# PCBWayPrototype.net
KiCad netlist of a schematic drawn in EAGLE
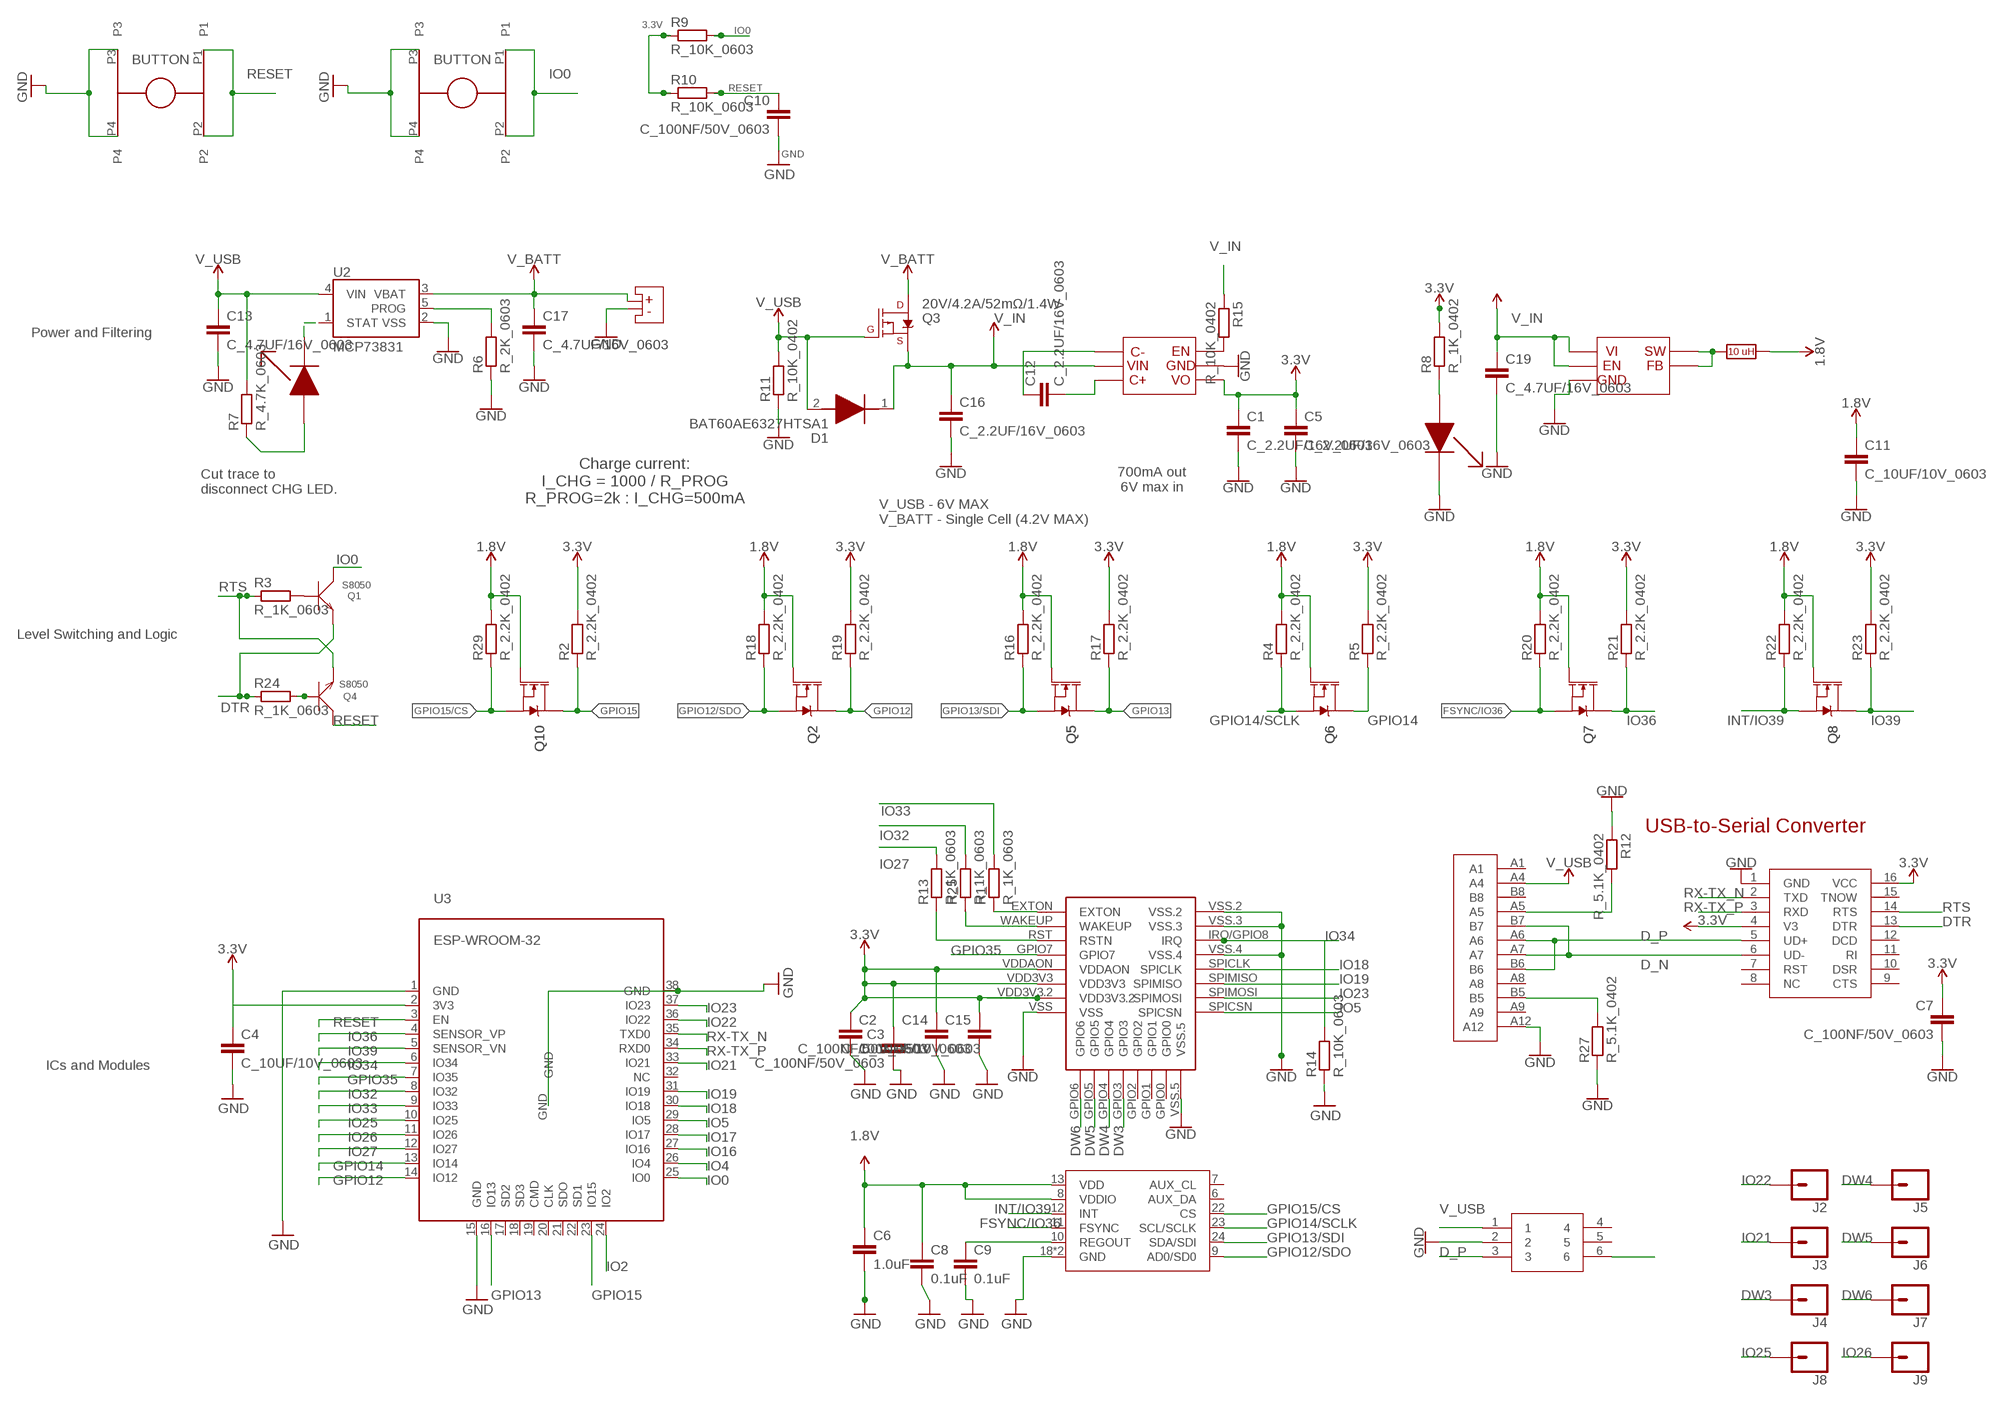
[diagram p0: schematic, sheet 1]

(export (version "E")
  (design (tool "Eeschema 10.0.6"))
  (components
    (comp (ref "C1")
      (value "C_2.2UF/16V_0603")
      (footprint "eagle-import:C0603")
      (fields (field (name "LCSC_PART") "C23630"))
      (libsource (lib "eagle-import") (part "C__06032.2UF/16V"))
    )
    (comp (ref "C2")
      (value "C_10UF/10V_0603")
      (footprint "eagle-import:C0603")
      (fields (field (name "LCSC_PART") "C19702"))
      (libsource (lib "eagle-import") (part "C__060310UF/10V"))
    )
    (comp (ref "C3")
      (value "C_100NF/50V_0603")
      (footprint "eagle-import:C0603")
      (fields (field (name "LCSC_PART") "C14663"))
      (libsource (lib "eagle-import") (part "C__0603100NF/50V"))
    )
    (comp (ref "C4")
      (value "C_10UF/10V_0603")
      (footprint "eagle-import:C0603")
      (fields (field (name "LCSC_PART") "C19702"))
      (libsource (lib "eagle-import") (part "C__060310UF/10V"))
    )
    (comp (ref "C5")
      (value "C_2.2UF/16V_0603")
      (footprint "eagle-import:C0603")
      (fields (field (name "LCSC_PART") "C23630"))
      (libsource (lib "eagle-import") (part "C__06032.2UF/16V"))
    )
    (comp (ref "C6")
      (value "1.0uF")
      (footprint "eagle-import:0603")
      (libsource (lib "eagle-import") (part "1.0UF-0603-16V-10%-X7R"))
    )
    (comp (ref "C7")
      (value "C_100NF/50V_0603")
      (footprint "eagle-import:C0603")
      (fields (field (name "LCSC_PART") "C14663"))
      (libsource (lib "eagle-import") (part "C__0603100NF/50V"))
    )
    (comp (ref "C8")
      (value "0.1uF")
      (footprint "eagle-import:0603")
      (libsource (lib "eagle-import") (part "0.1UF-0603-25V-5%"))
    )
    (comp (ref "C9")
      (value "0.1uF")
      (footprint "eagle-import:0603")
      (libsource (lib "eagle-import") (part "0.1UF-0603-25V-5%"))
    )
    (comp (ref "C10")
      (value "C_100NF/50V_0603")
      (footprint "eagle-import:C0603")
      (fields (field (name "LCSC_PART") "C14663"))
      (libsource (lib "eagle-import") (part "C__0603100NF/50V"))
    )
    (comp (ref "C11")
      (value "C_10UF/10V_0603")
      (footprint "eagle-import:C0603")
      (fields (field (name "LCSC_PART") "C19702"))
      (libsource (lib "eagle-import") (part "C__060310UF/10V"))
    )
    (comp (ref "C12")
      (value "C_2.2UF/16V_0603")
      (footprint "eagle-import:C0603")
      (fields (field (name "LCSC_PART") "C23630"))
      (libsource (lib "eagle-import") (part "C__06032.2UF/16V"))
    )
    (comp (ref "C13")
      (value "C_4.7UF/16V_0603")
      (footprint "eagle-import:C0603")
      (fields (field (name "LCSC_PART") "C19666"))
      (libsource (lib "eagle-import") (part "C__06034.7UF/16V"))
    )
    (comp (ref "C14")
      (value "C_100NF/50V_0603")
      (footprint "eagle-import:C0603")
      (fields (field (name "LCSC_PART") "C14663"))
      (libsource (lib "eagle-import") (part "C__0603100NF/50V"))
    )
    (comp (ref "C15")
      (value "C_100NF/50V_0603")
      (footprint "eagle-import:C0603")
      (fields (field (name "LCSC_PART") "C14663"))
      (libsource (lib "eagle-import") (part "C__0603100NF/50V"))
    )
    (comp (ref "C16")
      (value "C_2.2UF/16V_0603")
      (footprint "eagle-import:C0603")
      (fields (field (name "LCSC_PART") "C23630"))
      (libsource (lib "eagle-import") (part "C__06032.2UF/16V"))
    )
    (comp (ref "C17")
      (value "C_4.7UF/16V_0603")
      (footprint "eagle-import:C0603")
      (fields (field (name "LCSC_PART") "C19666"))
      (libsource (lib "eagle-import") (part "C__06034.7UF/16V"))
    )
    (comp (ref "C19")
      (value "C_4.7UF/16V_0603")
      (footprint "eagle-import:C0603")
      (fields (field (name "LCSC_PART") "C19666"))
      (libsource (lib "eagle-import") (part "C__06034.7UF/16V"))
    )
    (comp (ref "D1")
      (value "BAT60AE6327HTSA1")
      (footprint "eagle-import:SOD2513X110N")
      (fields (field (name "MOUSER_PART_NUMBER") "726-BAT60AE6327HTSA1"))
      (libsource (lib "eagle-import") (part "BAT60AE6327HTSA1"))
    )
    (comp (ref "J2")
      (value "CONN_01PTH_2MM")
      (footprint "eagle-import:1X01_2MM")
      (libsource (lib "eagle-import") (part "CONN_01PTH_2MM"))
    )
    (comp (ref "J3")
      (value "CONN_01PTH_2MM")
      (footprint "eagle-import:1X01_2MM")
      (libsource (lib "eagle-import") (part "CONN_01PTH_2MM"))
    )
    (comp (ref "J4")
      (value "CONN_01PTH_2MM")
      (footprint "eagle-import:1X01_2MM")
      (libsource (lib "eagle-import") (part "CONN_01PTH_2MM"))
    )
    (comp (ref "J5")
      (value "CONN_01PTH_2MM")
      (footprint "eagle-import:1X01_2MM")
      (libsource (lib "eagle-import") (part "CONN_01PTH_2MM"))
    )
    (comp (ref "J6")
      (value "CONN_01PTH_2MM")
      (footprint "eagle-import:1X01_2MM")
      (libsource (lib "eagle-import") (part "CONN_01PTH_2MM"))
    )
    (comp (ref "J7")
      (value "CONN_01PTH_2MM")
      (footprint "eagle-import:1X01_2MM")
      (libsource (lib "eagle-import") (part "CONN_01PTH_2MM"))
    )
    (comp (ref "J8")
      (value "CONN_01PTH_2MM")
      (footprint "eagle-import:1X01_2MM")
      (libsource (lib "eagle-import") (part "CONN_01PTH_2MM"))
    )
    (comp (ref "J9")
      (value "CONN_01PTH_2MM")
      (footprint "eagle-import:1X01_2MM")
      (libsource (lib "eagle-import") (part "CONN_01PTH_2MM"))
    )
    (comp (ref "Q1")
      (value "S8050")
      (footprint "eagle-import:SOT23")
      (libsource (lib "eagle-import") (part "TRANSISTOR-NPN-SOT23"))
    )
    (comp (ref "Q2")
      (value "20V/0.2A/8MHz/1.2Ω/1Vth")
      (footprint "eagle-import:SOT-416FL")
      (libsource (lib "eagle-import") (part "MOSFET-NCH-RE1C002UN"))
    )
    (comp (ref "Q3")
      (value "20V/4.2A/52mΩ/1.4W")
      (footprint "eagle-import:SOT23-3@1")
      (libsource (lib "eagle-import") (part "MOSFET_PCH-DMG2305UX-7"))
    )
    (comp (ref "Q4")
      (value "S8050")
      (footprint "eagle-import:SOT23")
      (libsource (lib "eagle-import") (part "TRANSISTOR-NPN-SOT23"))
    )
    (comp (ref "Q5")
      (value "20V/0.2A/8MHz/1.2Ω/1Vth")
      (footprint "eagle-import:SOT-416FL")
      (libsource (lib "eagle-import") (part "MOSFET-NCH-RE1C002UN"))
    )
    (comp (ref "Q6")
      (value "20V/0.2A/8MHz/1.2Ω/1Vth")
      (footprint "eagle-import:SOT-416FL")
      (libsource (lib "eagle-import") (part "MOSFET-NCH-RE1C002UN"))
    )
    (comp (ref "Q7")
      (value "20V/0.2A/8MHz/1.2Ω/1Vth")
      (footprint "eagle-import:SOT-416FL")
      (libsource (lib "eagle-import") (part "MOSFET-NCH-RE1C002UN"))
    )
    (comp (ref "Q8")
      (value "20V/0.2A/8MHz/1.2Ω/1Vth")
      (footprint "eagle-import:SOT-416FL")
      (libsource (lib "eagle-import") (part "MOSFET-NCH-RE1C002UN"))
    )
    (comp (ref "Q10")
      (value "20V/0.2A/8MHz/1.2Ω/1Vth")
      (footprint "eagle-import:SOT-416FL")
      (libsource (lib "eagle-import") (part "MOSFET-NCH-RE1C002UN"))
    )
    (comp (ref "R1")
      (value "R_1K_0603")
      (footprint "eagle-import:R0603")
      (fields (field (name "LCSC_PART") "C21190"))
      (libsource (lib "eagle-import") (part "R__06031K"))
    )
    (comp (ref "R2")
      (value "R_2.2K_0402")
      (footprint "eagle-import:R0402")
      (fields (field (name "LCSC_PART") "C25879"))
      (libsource (lib "eagle-import") (part "R__04022.2K"))
    )
    (comp (ref "R3")
      (value "R_1K_0603")
      (footprint "eagle-import:R0603")
      (fields (field (name "LCSC_PART") "C21190"))
      (libsource (lib "eagle-import") (part "R__06031K"))
    )
    (comp (ref "R4")
      (value "R_2.2K_0402")
      (footprint "eagle-import:R0402")
      (fields (field (name "LCSC_PART") "C25879"))
      (libsource (lib "eagle-import") (part "R__04022.2K"))
    )
    (comp (ref "R5")
      (value "R_2.2K_0402")
      (footprint "eagle-import:R0402")
      (fields (field (name "LCSC_PART") "C25879"))
      (libsource (lib "eagle-import") (part "R__04022.2K"))
    )
    (comp (ref "R6")
      (value "R_2K_0603")
      (footprint "eagle-import:R0603")
      (fields (field (name "LCSC_PART") "C22975"))
      (libsource (lib "eagle-import") (part "R__06032K"))
    )
    (comp (ref "R7")
      (value "R_4.7K_0603")
      (footprint "eagle-import:R0603")
      (fields (field (name "LCSC_PART") "C23162"))
      (libsource (lib "eagle-import") (part "R__06034.7K"))
    )
    (comp (ref "R8")
      (value "R_1K_0402")
      (footprint "eagle-import:R0402")
      (fields (field (name "LCSC_PART") "C11702"))
      (libsource (lib "eagle-import") (part "R__04021K"))
    )
    (comp (ref "R9")
      (value "R_10K_0603")
      (footprint "eagle-import:R0603")
      (fields (field (name "LCSC_PART") "C25804"))
      (libsource (lib "eagle-import") (part "R__060310K"))
    )
    (comp (ref "R10")
      (value "R_10K_0603")
      (footprint "eagle-import:R0603")
      (fields (field (name "LCSC_PART") "C25804"))
      (libsource (lib "eagle-import") (part "R__060310K"))
    )
    (comp (ref "R11")
      (value "R_10K_0402")
      (footprint "eagle-import:R0402")
      (fields (field (name "LCSC_PART") "C25744"))
      (libsource (lib "eagle-import") (part "R__040210K"))
    )
    (comp (ref "R12")
      (value "R_5.1K_0402")
      (footprint "eagle-import:R0402")
      (fields (field (name "LCSC_PART") "C25905"))
      (libsource (lib "eagle-import") (part "R__04025.1K"))
    )
    (comp (ref "R13")
      (value "R_1K_0603")
      (footprint "eagle-import:R0603")
      (fields (field (name "LCSC_PART") "C21190"))
      (libsource (lib "eagle-import") (part "R__06031K"))
    )
    (comp (ref "R14")
      (value "R_10K_0603")
      (footprint "eagle-import:R0603")
      (fields (field (name "LCSC_PART") "C25804"))
      (libsource (lib "eagle-import") (part "R__060310K"))
    )
    (comp (ref "R15")
      (value "R_10K_0402")
      (footprint "eagle-import:R0402")
      (fields (field (name "LCSC_PART") "C25744"))
      (libsource (lib "eagle-import") (part "R__040210K"))
    )
    (comp (ref "R16")
      (value "R_2.2K_0402")
      (footprint "eagle-import:R0402")
      (fields (field (name "LCSC_PART") "C25879"))
      (libsource (lib "eagle-import") (part "R__04022.2K"))
    )
    (comp (ref "R17")
      (value "R_2.2K_0402")
      (footprint "eagle-import:R0402")
      (fields (field (name "LCSC_PART") "C25879"))
      (libsource (lib "eagle-import") (part "R__04022.2K"))
    )
    (comp (ref "R18")
      (value "R_2.2K_0402")
      (footprint "eagle-import:R0402")
      (fields (field (name "LCSC_PART") "C25879"))
      (libsource (lib "eagle-import") (part "R__04022.2K"))
    )
    (comp (ref "R19")
      (value "R_2.2K_0402")
      (footprint "eagle-import:R0402")
      (fields (field (name "LCSC_PART") "C25879"))
      (libsource (lib "eagle-import") (part "R__04022.2K"))
    )
    (comp (ref "R20")
      (value "R_2.2K_0402")
      (footprint "eagle-import:R0402")
      (fields (field (name "LCSC_PART") "C25879"))
      (libsource (lib "eagle-import") (part "R__04022.2K"))
    )
    (comp (ref "R21")
      (value "R_2.2K_0402")
      (footprint "eagle-import:R0402")
      (fields (field (name "LCSC_PART") "C25879"))
      (libsource (lib "eagle-import") (part "R__04022.2K"))
    )
    (comp (ref "R22")
      (value "R_2.2K_0402")
      (footprint "eagle-import:R0402")
      (fields (field (name "LCSC_PART") "C25879"))
      (libsource (lib "eagle-import") (part "R__04022.2K"))
    )
    (comp (ref "R23")
      (value "R_2.2K_0402")
      (footprint "eagle-import:R0402")
      (fields (field (name "LCSC_PART") "C25879"))
      (libsource (lib "eagle-import") (part "R__04022.2K"))
    )
    (comp (ref "R24")
      (value "R_1K_0603")
      (footprint "eagle-import:R0603")
      (fields (field (name "LCSC_PART") "C21190"))
      (libsource (lib "eagle-import") (part "R__06031K"))
    )
    (comp (ref "R25")
      (value "R_1K_0603")
      (footprint "eagle-import:R0603")
      (fields (field (name "LCSC_PART") "C21190"))
      (libsource (lib "eagle-import") (part "R__06031K"))
    )
    (comp (ref "R27")
      (value "R_5.1K_0402")
      (footprint "eagle-import:R0402")
      (fields (field (name "LCSC_PART") "C25905"))
      (libsource (lib "eagle-import") (part "R__04025.1K"))
    )
    (comp (ref "R29")
      (value "R_2.2K_0402")
      (footprint "eagle-import:R0402")
      (fields (field (name "LCSC_PART") "C25879"))
      (libsource (lib "eagle-import") (part "R__04022.2K"))
    )
    (comp (ref "U$1")
      (value "K2-6639SP-C4SC-04_C83206")
      (footprint "eagle-import:K2-6639SP-C4SC-04")
      (libsource (lib "eagle-import") (part "K2-6639SP-C4SC-04_C83206"))
    )
    (comp (ref "U$2")
      (value "MLF2012")
      (footprint "eagle-import:MLF2012")
      (libsource (lib "eagle-import") (part "MLF2012"))
    )
    (comp (ref "U$3")
      (value "K2-6639SP-C4SC-04_C83206")
      (footprint "eagle-import:K2-6639SP-C4SC-04")
      (libsource (lib "eagle-import") (part "K2-6639SP-C4SC-04_C83206"))
    )
    (comp (ref "U$4")
      (value "TPS62202DBVR")
      (footprint "eagle-import:TPS62202DBVR")
      (libsource (lib "eagle-import") (part "TPS62202DBVR"))
    )
    (comp (ref "U$5")
      (value "HE9008M6R")
      (footprint "eagle-import:HE9008M6R")
      (libsource (lib "eagle-import") (part "HE9008M6R"))
    )
    (comp (ref "U$6")
      (value "19-217/GHC-YR1S2/3T")
      (footprint "eagle-import:19-217_GHC-YR1S2_3T")
      (libsource (lib "eagle-import") (part "19-217/GHC-YR1S2/3T"))
    )
    (comp (ref "U$7")
      (value "TPSMF05CT1G")
      (footprint "eagle-import:TPSMF05CT1G")
      (libsource (lib "eagle-import") (part "TPSMF05CT1G"))
    )
    (comp (ref "U$8")
      (value "SM02B_PASS_TB_LF")
      (footprint "eagle-import:SM02B_PASS_TB_LF")
      (libsource (lib "eagle-import") (part "SM02B_PASS_TB_LF"))
    )
    (comp (ref "U$9")
      (value "19-217/GHC-YR1S2/3T")
      (footprint "eagle-import:19-217_GHC-YR1S2_3T")
      (libsource (lib "eagle-import") (part "19-217/GHC-YR1S2/3T"))
    )
    (comp (ref "U$10")
      (value "USBC19")
      (footprint "eagle-import:USBC19")
      (libsource (lib "eagle-import") (part "USBC19"))
    )
    (comp (ref "U$11")
      (value "CH340B")
      (footprint "eagle-import:SOP-16")
      (libsource (lib "eagle-import") (part "CH340B"))
    )
    (comp (ref "U$12")
      (value "ICM20948")
      (footprint "eagle-import:ICM20948")
      (libsource (lib "eagle-import") (part "ICM20948"))
    )
    (comp (ref "U2")
      (value "MCP73831")
      (footprint "eagle-import:SOT23-5")
      (libsource (lib "eagle-import") (part "MCP73831"))
    )
    (comp (ref "U3")
      (value "ESP-WROOM-32")
      (footprint "eagle-import:ESP-WROOM-32")
      (libsource (lib "eagle-import") (part "ESP-WROOM-32"))
    )
    (comp (ref "U5")
      (value "DWM1000")
      (footprint "eagle-import:DWM1000")
      (libsource (lib "eagle-import") (part "DWM1000"))
    )
  )
  (nets
    (net (code "1") (name "/DTR") (class "Default")
      (node (ref "Q1") (pin "2") (pinfunction "E_2") (pintype "passive"))
      (node (ref "R24") (pin "1") (pinfunction "1_1") (pintype "passive"))
      (node (ref "U$11") (pin "13") (pinfunction "DTR_13") (pintype "bidirectional"))
    )
    (net (code "2") (name "/DW3") (class "Default")
      (node (ref "J4") (pin "1") (pinfunction "1_1") (pintype "passive"))
      (node (ref "U5") (pin "GPIO3") (pinfunction "GPIO3_GPIO3") (pintype "bidirectional"))
    )
    (net (code "3") (name "/DW4") (class "Default")
      (node (ref "J5") (pin "1") (pinfunction "1_1") (pintype "passive"))
      (node (ref "U5") (pin "GPIO4") (pinfunction "GPIO4_GPIO4") (pintype "bidirectional"))
    )
    (net (code "4") (name "/DW5") (class "Default")
      (node (ref "J6") (pin "1") (pinfunction "1_1") (pintype "passive"))
      (node (ref "U5") (pin "GPIO5") (pinfunction "GPIO5_GPIO5") (pintype "bidirectional"))
    )
    (net (code "5") (name "/DW6") (class "Default")
      (node (ref "J7") (pin "1") (pinfunction "1_1") (pintype "passive"))
      (node (ref "U5") (pin "GPIO6") (pinfunction "GPIO6_GPIO6") (pintype "bidirectional"))
    )
    (net (code "6") (name "/D_N") (class "Default")
      (node (ref "U$10") (pin "A7") (pinfunction "A7_A7") (pintype "bidirectional"))
      (node (ref "U$10") (pin "B7") (pinfunction "B7_B7") (pintype "bidirectional"))
      (node (ref "U$11") (pin "6") (pinfunction "UD-_6") (pintype "bidirectional"))
      (node (ref "U$7") (pin "6") (pinfunction "6_6") (pintype "bidirectional"))
    )
    (net (code "7") (name "/D_P") (class "Default")
      (node (ref "U$10") (pin "A6") (pinfunction "A6_A6") (pintype "bidirectional"))
      (node (ref "U$10") (pin "B6") (pinfunction "B6_B6") (pintype "bidirectional"))
      (node (ref "U$11") (pin "5") (pinfunction "UD+_5") (pintype "bidirectional"))
      (node (ref "U$7") (pin "3") (pinfunction "3_3") (pintype "bidirectional"))
    )
    (net (code "8") (name "/GPIO14") (class "Default")
      (node (ref "Q6") (pin "3") (pinfunction "D_3") (pintype "bidirectional"))
      (node (ref "R5") (pin "1") (pinfunction "1_1") (pintype "passive"))
      (node (ref "U3") (pin "13") (pinfunction "IO14_13") (pintype "bidirectional"))
    )
    (net (code "9") (name "/GPIO14{slash}SCLK") (class "Default")
      (node (ref "Q6") (pin "2") (pinfunction "S_2") (pintype "bidirectional"))
      (node (ref "R4") (pin "1") (pinfunction "1_1") (pintype "passive"))
      (node (ref "U$12") (pin "23") (pinfunction "SCL/SCLK_23") (pintype "bidirectional"))
    )
    (net (code "10") (name "/GPIO35") (class "Default")
      (node (ref "U3") (pin "7") (pinfunction "IO35_7") (pintype "bidirectional"))
      (node (ref "U5") (pin "GPIO7") (pinfunction "GPIO7_GPIO7") (pintype "bidirectional"))
    )
    (net (code "11") (name "/INT{slash}IO39") (class "Default")
      (node (ref "Q8") (pin "2") (pinfunction "S_2") (pintype "bidirectional"))
      (node (ref "R22") (pin "1") (pinfunction "1_1") (pintype "passive"))
      (node (ref "U$12") (pin "12") (pinfunction "INT_12") (pintype "bidirectional"))
    )
    (net (code "12") (name "/IO0") (class "Default")
      (node (ref "Q1") (pin "3") (pinfunction "C_3") (pintype "passive"))
      (node (ref "R9") (pin "2") (pinfunction "2_2") (pintype "passive"))
      (node (ref "U$3") (pin "P1") (pinfunction "P1_P1") (pintype "bidirectional"))
      (node (ref "U$3") (pin "P2") (pinfunction "P2_P2") (pintype "bidirectional"))
      (node (ref "U3") (pin "25") (pinfunction "IO0_25") (pintype "bidirectional"))
    )
    (net (code "13") (name "/IO2") (class "Default")
      (node (ref "U3") (pin "24") (pinfunction "IO2_24") (pintype "bidirectional"))
    )
    (net (code "14") (name "/IO4") (class "Default")
      (node (ref "U3") (pin "26") (pinfunction "IO4_26") (pintype "bidirectional"))
    )
    (net (code "15") (name "/IO5") (class "Default")
      (node (ref "U3") (pin "29") (pinfunction "IO5_29") (pintype "bidirectional"))
      (node (ref "U5") (pin "SPICSN") (pinfunction "SPICSN_SPICSN") (pintype "bidirectional"))
    )
    (net (code "16") (name "/IO16") (class "Default")
      (node (ref "U3") (pin "27") (pinfunction "IO16_27") (pintype "bidirectional"))
    )
    (net (code "17") (name "/IO17") (class "Default")
      (node (ref "U3") (pin "28") (pinfunction "IO17_28") (pintype "bidirectional"))
    )
    (net (code "18") (name "/IO18") (class "Default")
      (node (ref "U3") (pin "30") (pinfunction "IO18_30") (pintype "bidirectional"))
      (node (ref "U5") (pin "SPICLK") (pinfunction "SPICLK_SPICLK") (pintype "bidirectional"))
    )
    (net (code "19") (name "/IO19") (class "Default")
      (node (ref "U3") (pin "31") (pinfunction "IO19_31") (pintype "bidirectional"))
      (node (ref "U5") (pin "SPIMISO") (pinfunction "SPIMISO_SPIMISO") (pintype "bidirectional"))
    )
    (net (code "20") (name "/IO21") (class "Default")
      (node (ref "J3") (pin "1") (pinfunction "1_1") (pintype "passive"))
      (node (ref "U3") (pin "33") (pinfunction "IO21_33") (pintype "bidirectional"))
    )
    (net (code "21") (name "/IO22") (class "Default")
      (node (ref "J2") (pin "1") (pinfunction "1_1") (pintype "passive"))
      (node (ref "U3") (pin "36") (pinfunction "IO22_36") (pintype "bidirectional"))
    )
    (net (code "22") (name "/IO23") (class "Default")
      (node (ref "U3") (pin "37") (pinfunction "IO23_37") (pintype "bidirectional"))
      (node (ref "U5") (pin "SPIMOSI") (pinfunction "SPIMOSI_SPIMOSI") (pintype "bidirectional"))
    )
    (net (code "23") (name "/IO25") (class "Default")
      (node (ref "J8") (pin "1") (pinfunction "1_1") (pintype "passive"))
      (node (ref "U3") (pin "10") (pinfunction "IO25_10") (pintype "bidirectional"))
    )
    (net (code "24") (name "/IO26") (class "Default")
      (node (ref "J9") (pin "1") (pinfunction "1_1") (pintype "passive"))
      (node (ref "U3") (pin "11") (pinfunction "IO26_11") (pintype "bidirectional"))
    )
    (net (code "25") (name "/IO27") (class "Default")
      (node (ref "R13") (pin "2") (pinfunction "2_2") (pintype "passive"))
      (node (ref "U3") (pin "12") (pinfunction "IO27_12") (pintype "bidirectional"))
    )
    (net (code "26") (name "/IO32") (class "Default")
      (node (ref "R25") (pin "2") (pinfunction "2_2") (pintype "passive"))
      (node (ref "U3") (pin "8") (pinfunction "IO32_8") (pintype "bidirectional"))
    )
    (net (code "27") (name "/IO33") (class "Default")
      (node (ref "R1") (pin "2") (pinfunction "2_2") (pintype "passive"))
      (node (ref "U3") (pin "9") (pinfunction "IO33_9") (pintype "bidirectional"))
    )
    (net (code "28") (name "/IO34") (class "Default")
      (node (ref "R14") (pin "2") (pinfunction "2_2") (pintype "passive"))
      (node (ref "U3") (pin "6") (pinfunction "IO34_6") (pintype "bidirectional"))
      (node (ref "U5") (pin "IRQ/GPIO8") (pinfunction "IRQ_IRQ/GPIO8") (pintype "bidirectional"))
    )
    (net (code "29") (name "/IO36") (class "Default")
      (node (ref "Q7") (pin "3") (pinfunction "D_3") (pintype "bidirectional"))
      (node (ref "R21") (pin "1") (pinfunction "1_1") (pintype "passive"))
      (node (ref "U3") (pin "4") (pinfunction "SENSOR_VP_4") (pintype "bidirectional"))
    )
    (net (code "30") (name "/IO39") (class "Default")
      (node (ref "Q8") (pin "3") (pinfunction "D_3") (pintype "bidirectional"))
      (node (ref "R23") (pin "1") (pinfunction "1_1") (pintype "passive"))
      (node (ref "U3") (pin "5") (pinfunction "SENSOR_VN_5") (pintype "bidirectional"))
    )
    (net (code "31") (name "/RESET") (class "Default")
      (node (ref "C10") (pin "1") (pinfunction "1_1") (pintype "passive"))
      (node (ref "Q4") (pin "3") (pinfunction "C_3") (pintype "passive"))
      (node (ref "R10") (pin "2") (pinfunction "2_2") (pintype "passive"))
      (node (ref "U$1") (pin "P1") (pinfunction "P1_P1") (pintype "bidirectional"))
      (node (ref "U$1") (pin "P2") (pinfunction "P2_P2") (pintype "bidirectional"))
      (node (ref "U3") (pin "3") (pinfunction "EN_3") (pintype "bidirectional"))
    )
    (net (code "32") (name "/RTS") (class "Default")
      (node (ref "Q4") (pin "2") (pinfunction "E_2") (pintype "passive"))
      (node (ref "R3") (pin "1") (pinfunction "1_1") (pintype "passive"))
      (node (ref "U$11") (pin "14") (pinfunction "RTS_14") (pintype "bidirectional"))
    )
    (net (code "33") (name "/RX-TX_N") (class "Default")
      (node (ref "U$11") (pin "2") (pinfunction "TXD_2") (pintype "bidirectional"))
      (node (ref "U3") (pin "35") (pinfunction "TXD0_35") (pintype "bidirectional"))
    )
    (net (code "34") (name "/RX-TX_P") (class "Default")
      (node (ref "U$11") (pin "3") (pinfunction "RXD_3") (pintype "bidirectional"))
      (node (ref "U3") (pin "34") (pinfunction "RXD0_34") (pintype "bidirectional"))
    )
    (net (code "35") (name "1.8V") (class "Default")
      (node (ref "C11") (pin "1") (pinfunction "1_1") (pintype "passive"))
      (node (ref "C6") (pin "1") (pinfunction "1_1") (pintype "passive"))
      (node (ref "C8") (pin "1") (pinfunction "1_1") (pintype "passive"))
      (node (ref "Q10") (pin "1") (pinfunction "G_1") (pintype "bidirectional"))
      (node (ref "Q2") (pin "1") (pinfunction "G_1") (pintype "bidirectional"))
      (node (ref "Q5") (pin "1") (pinfunction "G_1") (pintype "bidirectional"))
      (node (ref "Q6") (pin "1") (pinfunction "G_1") (pintype "bidirectional"))
      (node (ref "Q7") (pin "1") (pinfunction "G_1") (pintype "bidirectional"))
      (node (ref "Q8") (pin "1") (pinfunction "G_1") (pintype "bidirectional"))
      (node (ref "R16") (pin "2") (pinfunction "2_2") (pintype "passive"))
      (node (ref "R18") (pin "2") (pinfunction "2_2") (pintype "passive"))
      (node (ref "R20") (pin "2") (pinfunction "2_2") (pintype "passive"))
      (node (ref "R22") (pin "2") (pinfunction "2_2") (pintype "passive"))
      (node (ref "R29") (pin "2") (pinfunction "2_2") (pintype "passive"))
      (node (ref "R4") (pin "2") (pinfunction "2_2") (pintype "passive"))
      (node (ref "U$12") (pin "13") (pinfunction "VDD_13") (pintype "bidirectional"))
      (node (ref "U$12") (pin "8") (pinfunction "VDDIO_8") (pintype "bidirectional"))
      (node (ref "U$2") (pin "2") (pinfunction "P$2_2") (pintype "bidirectional"))
    )
    (net (code "36") (name "3.3V") (class "Default")
      (node (ref "C1") (pin "1") (pinfunction "1_1") (pintype "passive"))
      (node (ref "C14") (pin "1") (pinfunction "1_1") (pintype "passive"))
      (node (ref "C15") (pin "1") (pinfunction "1_1") (pintype "passive"))
      (node (ref "C2") (pin "1") (pinfunction "1_1") (pintype "passive"))
      (node (ref "C3") (pin "1") (pinfunction "1_1") (pintype "passive"))
      (node (ref "C4") (pin "1") (pinfunction "1_1") (pintype "passive"))
      (node (ref "C5") (pin "1") (pinfunction "1_1") (pintype "passive"))
      (node (ref "C7") (pin "1") (pinfunction "1_1") (pintype "passive"))
      (node (ref "R10") (pin "1") (pinfunction "1_1") (pintype "passive"))
      (node (ref "R17") (pin "2") (pinfunction "2_2") (pintype "passive"))
      (node (ref "R19") (pin "2") (pinfunction "2_2") (pintype "passive"))
      (node (ref "R2") (pin "2") (pinfunction "2_2") (pintype "passive"))
      (node (ref "R21") (pin "2") (pinfunction "2_2") (pintype "passive"))
      (node (ref "R23") (pin "2") (pinfunction "2_2") (pintype "passive"))
      (node (ref "R5") (pin "2") (pinfunction "2_2") (pintype "passive"))
      (node (ref "R8") (pin "2") (pinfunction "2_2") (pintype "passive"))
      (node (ref "R9") (pin "1") (pinfunction "1_1") (pintype "passive"))
      (node (ref "U$11") (pin "16") (pinfunction "VCC_16") (pintype "bidirectional"))
      (node (ref "U$11") (pin "4") (pinfunction "V3_4") (pintype "bidirectional"))
      (node (ref "U$5") (pin "VOUT") (pinfunction "VO_VOUT") (pintype "bidirectional"))
      (node (ref "U3") (pin "2") (pinfunction "3V3_2") (pintype "bidirectional"))
      (node (ref "U5") (pin "VDD3V3") (pinfunction "VDD3V3_VDD3V3") (pintype "bidirectional"))
      (node (ref "U5") (pin "VDD3V3.2") (pinfunction "VDD3V3.2_VDD3V3.2") (pintype "bidirectional"))
      (node (ref "U5") (pin "VDDAON") (pinfunction "VDDAON_VDDAON") (pintype "bidirectional"))
    )
    (net (code "37") (name "FSYNC{slash}IO36") (class "Default")
      (node (ref "Q7") (pin "2") (pinfunction "S_2") (pintype "bidirectional"))
      (node (ref "R20") (pin "1") (pinfunction "1_1") (pintype "passive"))
      (node (ref "U$12") (pin "11") (pinfunction "FSYNC_11") (pintype "bidirectional"))
    )
    (net (code "38") (name "GND") (class "Default")
      (node (ref "C1") (pin "2") (pinfunction "2_2") (pintype "passive"))
      (node (ref "C10") (pin "2") (pinfunction "2_2") (pintype "passive"))
      (node (ref "C11") (pin "2") (pinfunction "2_2") (pintype "passive"))
      (node (ref "C13") (pin "2") (pinfunction "2_2") (pintype "passive"))
      (node (ref "C14") (pin "2") (pinfunction "2_2") (pintype "passive"))
      (node (ref "C15") (pin "2") (pinfunction "2_2") (pintype "passive"))
      (node (ref "C16") (pin "2") (pinfunction "2_2") (pintype "passive"))
      (node (ref "C17") (pin "2") (pinfunction "2_2") (pintype "passive"))
      (node (ref "C19") (pin "2") (pinfunction "2_2") (pintype "passive"))
      (node (ref "C2") (pin "2") (pinfunction "2_2") (pintype "passive"))
      (node (ref "C3") (pin "2") (pinfunction "2_2") (pintype "passive"))
      (node (ref "C4") (pin "2") (pinfunction "2_2") (pintype "passive"))
      (node (ref "C5") (pin "2") (pinfunction "2_2") (pintype "passive"))
      (node (ref "C6") (pin "2") (pinfunction "2_2") (pintype "passive"))
      (node (ref "C7") (pin "2") (pinfunction "2_2") (pintype "passive"))
      (node (ref "C8") (pin "2") (pinfunction "2_2") (pintype "passive"))
      (node (ref "C9") (pin "2") (pinfunction "2_2") (pintype "passive"))
      (node (ref "R11") (pin "1") (pinfunction "1_1") (pintype "passive"))
      (node (ref "R12") (pin "1") (pinfunction "1_1") (pintype "passive"))
      (node (ref "R14") (pin "1") (pinfunction "1_1") (pintype "passive"))
      (node (ref "R27") (pin "1") (pinfunction "1_1") (pintype "passive"))
      (node (ref "R6") (pin "1") (pinfunction "1_1") (pintype "passive"))
      (node (ref "U$1") (pin "P3") (pinfunction "P3_P3") (pintype "bidirectional"))
      (node (ref "U$1") (pin "P4") (pinfunction "P4_P4") (pintype "bidirectional"))
      (node (ref "U$10") (pin "A12") (pinfunction "A12_A12") (pintype "bidirectional"))
      (node (ref "U$11") (pin "1") (pinfunction "GND_1") (pintype "bidirectional"))
      (node (ref "U$12") (pin "18") (pinfunction "GND_18") (pintype "bidirectional"))
      (node (ref "U$12") (pin "20") (pinfunction "GND_20") (pintype "bidirectional"))
      (node (ref "U$3") (pin "P3") (pinfunction "P3_P3") (pintype "bidirectional"))
      (node (ref "U$3") (pin "P4") (pinfunction "P4_P4") (pintype "bidirectional"))
      (node (ref "U$4") (pin "2") (pinfunction "GND_2") (pintype "bidirectional"))
      (node (ref "U$5") (pin "GND") (pinfunction "GND_GND") (pintype "bidirectional"))
      (node (ref "U$7") (pin "2") (pinfunction "2_2") (pintype "bidirectional"))
      (node (ref "U$8") (pin "3") (pinfunction "-_3") (pintype "bidirectional"))
      (node (ref "U$9") (pin "1") (pinfunction "2_1") (pintype "bidirectional"))
      (node (ref "U2") (pin "2") (pinfunction "VSS_2") (pintype "power_in"))
      (node (ref "U3") (pin "1") (pinfunction "GND_1") (pintype "bidirectional"))
      (node (ref "U3") (pin "15") (pinfunction "GND_15") (pintype "bidirectional"))
      (node (ref "U3") (pin "38") (pinfunction "GND_38") (pintype "bidirectional"))
      (node (ref "U3") (pin "GND") (pinfunction "GND_GND") (pintype "bidirectional"))
      (node (ref "U5") (pin "VSS") (pinfunction "VSS_VSS") (pintype "bidirectional"))
      (node (ref "U5") (pin "VSS.2") (pinfunction "VSS.2_VSS.2") (pintype "bidirectional"))
      (node (ref "U5") (pin "VSS.3") (pinfunction "VSS.3_VSS.3") (pintype "bidirectional"))
      (node (ref "U5") (pin "VSS.4") (pinfunction "VSS.4_VSS.4") (pintype "bidirectional"))
      (node (ref "U5") (pin "VSS.5") (pinfunction "VSS.5_VSS.5") (pintype "bidirectional"))
    )
    (net (code "39") (name "GPIO12") (class "Default")
      (node (ref "Q2") (pin "3") (pinfunction "D_3") (pintype "bidirectional"))
      (node (ref "R19") (pin "1") (pinfunction "1_1") (pintype "passive"))
      (node (ref "U3") (pin "14") (pinfunction "IO12_14") (pintype "bidirectional"))
    )
    (net (code "40") (name "GPIO12{slash}SDO") (class "Default")
      (node (ref "Q2") (pin "2") (pinfunction "S_2") (pintype "bidirectional"))
      (node (ref "R18") (pin "1") (pinfunction "1_1") (pintype "passive"))
      (node (ref "U$12") (pin "9") (pinfunction "AD0/SD0_9") (pintype "bidirectional"))
    )
    (net (code "41") (name "GPIO13") (class "Default")
      (node (ref "Q5") (pin "3") (pinfunction "D_3") (pintype "bidirectional"))
      (node (ref "R17") (pin "1") (pinfunction "1_1") (pintype "passive"))
      (node (ref "U3") (pin "16") (pinfunction "IO13_16") (pintype "bidirectional"))
    )
    (net (code "42") (name "GPIO13{slash}SDI") (class "Default")
      (node (ref "Q5") (pin "2") (pinfunction "S_2") (pintype "bidirectional"))
      (node (ref "R16") (pin "1") (pinfunction "1_1") (pintype "passive"))
      (node (ref "U$12") (pin "24") (pinfunction "SDA/SDI_24") (pintype "bidirectional"))
    )
    (net (code "43") (name "GPIO15") (class "Default")
      (node (ref "Q10") (pin "3") (pinfunction "D_3") (pintype "bidirectional"))
      (node (ref "R2") (pin "1") (pinfunction "1_1") (pintype "passive"))
      (node (ref "U3") (pin "23") (pinfunction "IO15_23") (pintype "bidirectional"))
    )
    (net (code "44") (name "GPIO15{slash}CS") (class "Default")
      (node (ref "Q10") (pin "2") (pinfunction "S_2") (pintype "bidirectional"))
      (node (ref "R29") (pin "1") (pinfunction "1_1") (pintype "passive"))
      (node (ref "U$12") (pin "22") (pinfunction "CS_22") (pintype "bidirectional"))
    )
    (net (code "45") (name "Net-(C12-Pad1)") (class "Default")
      (node (ref "C12") (pin "1") (pinfunction "1_1") (pintype "passive"))
      (node (ref "U$5") (pin "C-") (pinfunction "C-_C-") (pintype "bidirectional"))
    )
    (net (code "46") (name "Net-(C12-Pad2)") (class "Default")
      (node (ref "C12") (pin "2") (pinfunction "2_2") (pintype "passive"))
      (node (ref "U$5") (pin "C+") (pinfunction "C+_C+") (pintype "bidirectional"))
    )
    (net (code "47") (name "Net-(Q1-B)") (class "Default")
      (node (ref "Q1") (pin "1") (pinfunction "B_1") (pintype "passive"))
      (node (ref "R3") (pin "2") (pinfunction "2_2") (pintype "passive"))
    )
    (net (code "48") (name "Net-(Q4-B)") (class "Default")
      (node (ref "Q4") (pin "1") (pinfunction "B_1") (pintype "passive"))
      (node (ref "R24") (pin "2") (pinfunction "2_2") (pintype "passive"))
    )
    (net (code "49") (name "Net-(R1-Pad1)") (class "Default")
      (node (ref "R1") (pin "1") (pinfunction "1_1") (pintype "passive"))
      (node (ref "U5") (pin "EXTON") (pinfunction "EXTON_EXTON") (pintype "bidirectional"))
    )
    (net (code "50") (name "Net-(R12-Pad2)") (class "Default")
      (node (ref "R12") (pin "2") (pinfunction "2_2") (pintype "passive"))
      (node (ref "U$10") (pin "A5") (pinfunction "A5_A5") (pintype "bidirectional"))
    )
    (net (code "51") (name "Net-(R15-Pad2)") (class "Default")
      (node (ref "R15") (pin "2") (pinfunction "2_2") (pintype "passive"))
      (node (ref "U$5") (pin "EN") (pinfunction "EN_EN") (pintype "bidirectional"))
    )
    (net (code "52") (name "Net-(R25-Pad1)") (class "Default")
      (node (ref "R25") (pin "1") (pinfunction "1_1") (pintype "passive"))
      (node (ref "U5") (pin "WAKEUP") (pinfunction "WAKEUP_WAKEUP") (pintype "bidirectional"))
    )
    (net (code "53") (name "Net-(R27-Pad2)") (class "Default")
      (node (ref "R27") (pin "2") (pinfunction "2_2") (pintype "passive"))
      (node (ref "U$10") (pin "B5") (pinfunction "B5_B5") (pintype "bidirectional"))
    )
    (net (code "54") (name "Net-(U$2-P$1)") (class "Default")
      (node (ref "U$2") (pin "1") (pinfunction "P$1_1") (pintype "bidirectional"))
      (node (ref "U$4") (pin "4") (pinfunction "FB_4") (pintype "bidirectional"))
      (node (ref "U$4") (pin "5") (pinfunction "SW_5") (pintype "bidirectional"))
    )
    (net (code "55") (name "Net-(U$6-1)") (class "Default")
      (node (ref "R7") (pin "1") (pinfunction "1_1") (pintype "passive"))
      (node (ref "U$6") (pin "2") (pinfunction "1_2") (pintype "bidirectional"))
    )
    (net (code "56") (name "Net-(U$6-2)") (class "Default")
      (node (ref "U$6") (pin "1") (pinfunction "2_1") (pintype "bidirectional"))
      (node (ref "U2") (pin "1") (pinfunction "STAT_1") (pintype "output"))
    )
    (net (code "57") (name "Net-(U$9-1)") (class "Default")
      (node (ref "R8") (pin "1") (pinfunction "1_1") (pintype "passive"))
      (node (ref "U$9") (pin "2") (pinfunction "1_2") (pintype "bidirectional"))
    )
    (net (code "58") (name "Net-(U$12-REGOUT)") (class "Default")
      (node (ref "C9") (pin "1") (pinfunction "1_1") (pintype "passive"))
      (node (ref "U$12") (pin "10") (pinfunction "REGOUT_10") (pintype "bidirectional"))
    )
    (net (code "59") (name "Net-(U2-PROG)") (class "Default")
      (node (ref "R6") (pin "2") (pinfunction "2_2") (pintype "passive"))
      (node (ref "U2") (pin "5") (pinfunction "PROG_5") (pintype "input"))
    )
    (net (code "60") (name "Net-(U5-RSTN)") (class "Default")
      (node (ref "R13") (pin "1") (pinfunction "1_1") (pintype "passive"))
      (node (ref "U5") (pin "RST") (pinfunction "RSTN_RST") (pintype "bidirectional"))
    )
    (net (code "61") (name "VIN") (class "Default")
      (node (ref "C16") (pin "1") (pinfunction "1_1") (pintype "passive"))
      (node (ref "C19") (pin "1") (pinfunction "1_1") (pintype "passive"))
      (node (ref "D1") (pin "1") (pinfunction "K_1") (pintype "bidirectional"))
      (node (ref "Q3") (pin "2") (pinfunction "S_2") (pintype "bidirectional"))
      (node (ref "R15") (pin "1") (pinfunction "1_1") (pintype "passive"))
      (node (ref "U$4") (pin "1") (pinfunction "VI_1") (pintype "bidirectional"))
      (node (ref "U$4") (pin "3") (pinfunction "EN_3") (pintype "bidirectional"))
      (node (ref "U$5") (pin "VIN") (pinfunction "VIN_VIN") (pintype "bidirectional"))
    )
    (net (code "62") (name "V_BATT") (class "Default")
      (node (ref "C17") (pin "1") (pinfunction "1_1") (pintype "passive"))
      (node (ref "Q3") (pin "3") (pinfunction "D_3") (pintype "bidirectional"))
      (node (ref "U$8") (pin "4") (pinfunction "+_4") (pintype "bidirectional"))
      (node (ref "U2") (pin "3") (pinfunction "VBAT_3") (pintype "power_in"))
    )
    (net (code "63") (name "V_USB") (class "Default")
      (node (ref "C13") (pin "1") (pinfunction "1_1") (pintype "passive"))
      (node (ref "D1") (pin "2") (pinfunction "A_2") (pintype "bidirectional"))
      (node (ref "Q3") (pin "1") (pinfunction "G_1") (pintype "bidirectional"))
      (node (ref "R11") (pin "2") (pinfunction "2_2") (pintype "passive"))
      (node (ref "R7") (pin "2") (pinfunction "2_2") (pintype "passive"))
      (node (ref "U$10") (pin "A4") (pinfunction "A4_A4") (pintype "bidirectional"))
      (node (ref "U$7") (pin "1") (pinfunction "1_1") (pintype "bidirectional"))
      (node (ref "U2") (pin "4") (pinfunction "VIN_4") (pintype "power_in"))
    )
    (net (code "64") (name "unconnected-(U$7-Pad4)") (class "Default")
      (node (ref "U$7") (pin "4") (pinfunction "4_4") (pintype "bidirectional"))
    )
    (net (code "65") (name "unconnected-(U$7-Pad5)") (class "Default")
      (node (ref "U$7") (pin "5") (pinfunction "5_5") (pintype "bidirectional"))
    )
    (net (code "66") (name "unconnected-(U$10-PadA1)") (class "Default")
      (node (ref "U$10") (pin "A1") (pinfunction "A1_A1") (pintype "bidirectional"))
    )
    (net (code "67") (name "unconnected-(U$10-PadA8)") (class "Default")
      (node (ref "U$10") (pin "A8") (pinfunction "A8_A8") (pintype "bidirectional"))
    )
    (net (code "68") (name "unconnected-(U$10-PadA9)") (class "Default")
      (node (ref "U$10") (pin "A9") (pinfunction "A9_A9") (pintype "bidirectional"))
    )
    (net (code "69") (name "unconnected-(U$10-PadB8)") (class "Default")
      (node (ref "U$10") (pin "B8") (pinfunction "B8_B8") (pintype "bidirectional"))
    )
    (net (code "70") (name "unconnected-(U$11-CTS-Pad9)") (class "Default")
      (node (ref "U$11") (pin "9") (pinfunction "CTS_9") (pintype "bidirectional"))
    )
    (net (code "71") (name "unconnected-(U$11-DCD-Pad12)") (class "Default")
      (node (ref "U$11") (pin "12") (pinfunction "DCD_12") (pintype "bidirectional"))
    )
    (net (code "72") (name "unconnected-(U$11-DSR-Pad10)") (class "Default")
      (node (ref "U$11") (pin "10") (pinfunction "DSR_10") (pintype "bidirectional"))
    )
    (net (code "73") (name "unconnected-(U$11-NC-Pad8)") (class "Default")
      (node (ref "U$11") (pin "8") (pinfunction "NC_8") (pintype "bidirectional"))
    )
    (net (code "74") (name "unconnected-(U$11-RI-Pad11)") (class "Default")
      (node (ref "U$11") (pin "11") (pinfunction "RI_11") (pintype "bidirectional"))
    )
    (net (code "75") (name "unconnected-(U$11-RST-Pad7)") (class "Default")
      (node (ref "U$11") (pin "7") (pinfunction "RST_7") (pintype "bidirectional"))
    )
    (net (code "76") (name "unconnected-(U$11-TNOW-Pad15)") (class "Default")
      (node (ref "U$11") (pin "15") (pinfunction "TNOW_15") (pintype "bidirectional"))
    )
    (net (code "77") (name "unconnected-(U$12-AUX_CL-Pad7)") (class "Default")
      (node (ref "U$12") (pin "7") (pinfunction "AUX_CL_7") (pintype "bidirectional"))
    )
    (net (code "78") (name "unconnected-(U$12-AUX_DA-Pad6)") (class "Default")
      (node (ref "U$12") (pin "6") (pinfunction "AUX_DA_6") (pintype "bidirectional"))
    )
    (net (code "79") (name "unconnected-(U3-CLK-Pad20)") (class "Default")
      (node (ref "U3") (pin "20") (pinfunction "CLK_20") (pintype "bidirectional"))
    )
    (net (code "80") (name "unconnected-(U3-CMD-Pad19)") (class "Default")
      (node (ref "U3") (pin "19") (pinfunction "CMD_19") (pintype "bidirectional"))
    )
    (net (code "81") (name "unconnected-(U3-NC-Pad32)") (class "Default")
      (node (ref "U3") (pin "32") (pinfunction "NC_32") (pintype "bidirectional"))
    )
    (net (code "82") (name "unconnected-(U3-SD1-Pad22)") (class "Default")
      (node (ref "U3") (pin "22") (pinfunction "SD1_22") (pintype "bidirectional"))
    )
    (net (code "83") (name "unconnected-(U3-SD2-Pad17)") (class "Default")
      (node (ref "U3") (pin "17") (pinfunction "SD2_17") (pintype "bidirectional"))
    )
    (net (code "84") (name "unconnected-(U3-SD3-Pad18)") (class "Default")
      (node (ref "U3") (pin "18") (pinfunction "SD3_18") (pintype "bidirectional"))
    )
    (net (code "85") (name "unconnected-(U3-SDO-Pad21)") (class "Default")
      (node (ref "U3") (pin "21") (pinfunction "SDO_21") (pintype "bidirectional"))
    )
    (net (code "86") (name "unconnected-(U5-PadGPIO0)") (class "Default")
      (node (ref "U5") (pin "GPIO0") (pinfunction "GPIO0_GPIO0") (pintype "bidirectional"))
    )
    (net (code "87") (name "unconnected-(U5-PadGPIO1)") (class "Default")
      (node (ref "U5") (pin "GPIO1") (pinfunction "GPIO1_GPIO1") (pintype "bidirectional"))
    )
    (net (code "88") (name "unconnected-(U5-PadGPIO2)") (class "Default")
      (node (ref "U5") (pin "GPIO2") (pinfunction "GPIO2_GPIO2") (pintype "bidirectional"))
    )
  )
)
